# output_leds.net
KiCad netlist of a schematic drawn in Altium Designer
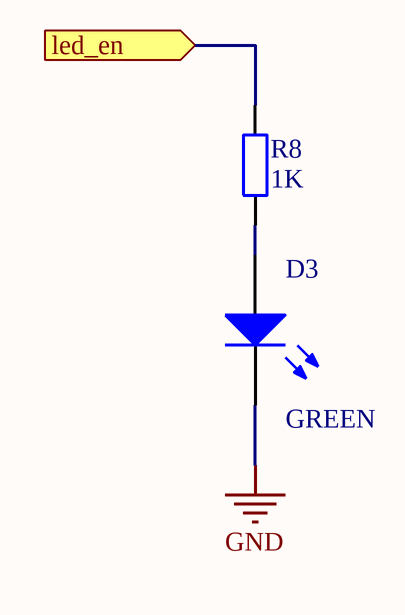
[diagram p0: output leds.SchDoc]

(export (version "E")
  (design (tool "Eeschema 10.0.6"))
  (components
    (comp (ref "D3")
      (value "GREEN")
      (footprint "LGQ971")
      (description "Typical RED, GREEN, YELLOW, AMBER GaAs LED")
      (libsource (lib "Miscellaneous Devices") (part "LED2"))
    )
    (comp (ref "R8")
      (value "1K")
      (footprint "R0603")
      (description "Resistor")
      (fields (field (name "Comment") "Res"))
      (libsource (lib "Miscellaneous Devices") (part "Res2"))
    )
  )
  (nets
    (net (code "1") (name "/led_en") (class "Default")
      (node (ref "R8") (pin "2") (pinfunction "2_2") (pintype "passive"))
    )
    (net (code "2") (name "GND") (class "Default")
      (node (ref "D3") (pin "2") (pinfunction "K_2") (pintype "passive"))
    )
    (net (code "3") (name "Net-(D3-A)") (class "Default")
      (node (ref "D3") (pin "1") (pinfunction "A_1") (pintype "passive"))
      (node (ref "R8") (pin "1") (pinfunction "1_1") (pintype "passive"))
    )
  )
)
